# peripherals.net
KiCad netlist of a schematic drawn in Altium Designer
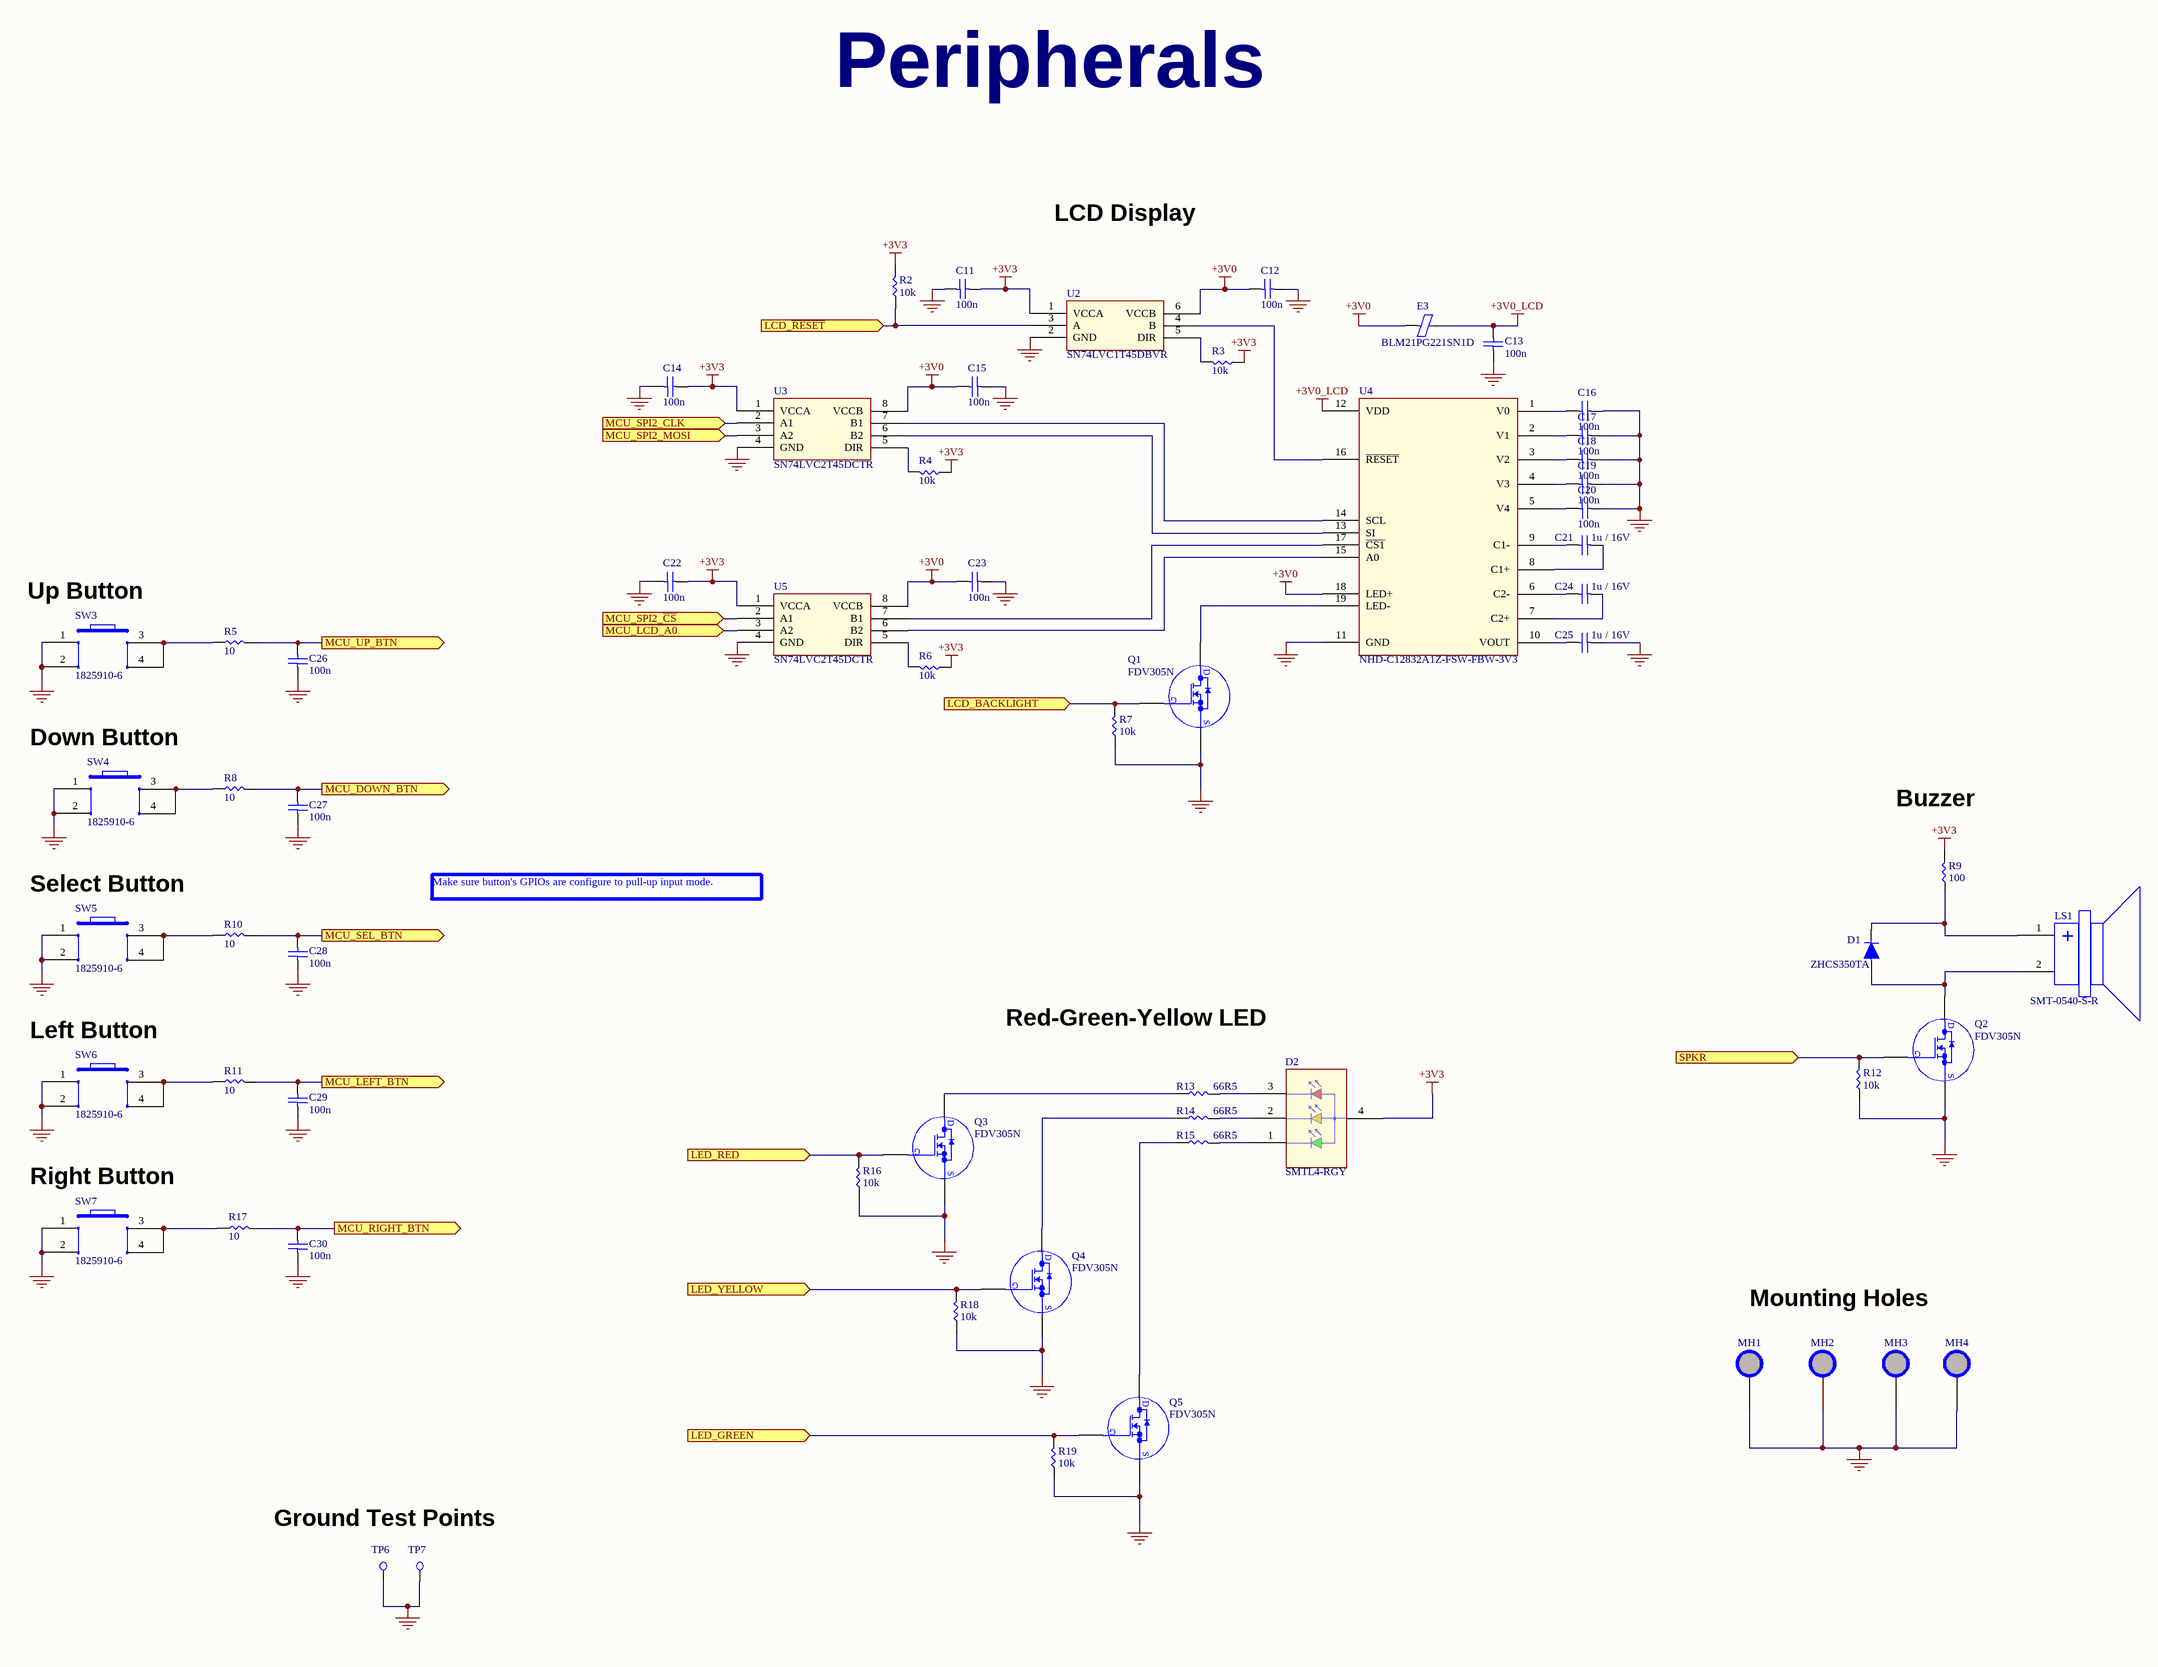
[diagram p0: peripherals.SchDoc]

(export (version "E")
  (design (tool "Eeschema 10.0.6"))
  (components
    (comp (ref "C11")
      (value "100n")
      (footprint "C0402")
      (fields
        (field (name "MANUFACTURER") "TDK")
        (field (name "PCN PART NUMBER") "MLCC Part Number Change 30/Nov/2012")
        (field (name "TOLERANCE") "±10%")
      )
      (libsource (lib "rookieboard_symbols") (part "CGA2B3X7R1E104K050BB"))
    )
    (comp (ref "C12")
      (value "100n")
      (footprint "C0402")
      (fields
        (field (name "MANUFACTURER") "TDK")
        (field (name "PCN PART NUMBER") "MLCC Part Number Change 30/Nov/2012")
        (field (name "TOLERANCE") "±10%")
      )
      (libsource (lib "rookieboard_symbols") (part "CGA2B3X7R1E104K050BB"))
    )
    (comp (ref "C13")
      (value "100n")
      (footprint "C0402")
      (fields
        (field (name "MANUFACTURER") "TDK")
        (field (name "PCN PART NUMBER") "MLCC Part Number Change 30/Nov/2012")
        (field (name "TOLERANCE") "±10%")
      )
      (libsource (lib "rookieboard_symbols") (part "CGA2B3X7R1E104K050BB"))
    )
    (comp (ref "C14")
      (value "100n")
      (footprint "C0402")
      (fields
        (field (name "MANUFACTURER") "TDK")
        (field (name "PCN PART NUMBER") "MLCC Part Number Change 30/Nov/2012")
        (field (name "TOLERANCE") "±10%")
      )
      (libsource (lib "rookieboard_symbols") (part "CGA2B3X7R1E104K050BB"))
    )
    (comp (ref "C15")
      (value "100n")
      (footprint "C0402")
      (fields
        (field (name "MANUFACTURER") "TDK")
        (field (name "PCN PART NUMBER") "MLCC Part Number Change 30/Nov/2012")
        (field (name "TOLERANCE") "±10%")
      )
      (libsource (lib "rookieboard_symbols") (part "CGA2B3X7R1E104K050BB"))
    )
    (comp (ref "C16")
      (value "100n")
      (footprint "C0402")
      (fields
        (field (name "MANUFACTURER") "TDK")
        (field (name "PCN PART NUMBER") "MLCC Part Number Change 30/Nov/2012")
        (field (name "TOLERANCE") "±10%")
      )
      (libsource (lib "rookieboard_symbols") (part "CGA2B3X7R1E104K050BB"))
    )
    (comp (ref "C17")
      (value "100n")
      (footprint "C0402")
      (fields
        (field (name "MANUFACTURER") "TDK")
        (field (name "PCN PART NUMBER") "MLCC Part Number Change 30/Nov/2012")
        (field (name "TOLERANCE") "±10%")
      )
      (libsource (lib "rookieboard_symbols") (part "CGA2B3X7R1E104K050BB"))
    )
    (comp (ref "C18")
      (value "100n")
      (footprint "C0402")
      (fields
        (field (name "MANUFACTURER") "TDK")
        (field (name "PCN PART NUMBER") "MLCC Part Number Change 30/Nov/2012")
        (field (name "TOLERANCE") "±10%")
      )
      (libsource (lib "rookieboard_symbols") (part "CGA2B3X7R1E104K050BB"))
    )
    (comp (ref "C19")
      (value "100n")
      (footprint "C0402")
      (fields
        (field (name "MANUFACTURER") "TDK")
        (field (name "PCN PART NUMBER") "MLCC Part Number Change 30/Nov/2012")
        (field (name "TOLERANCE") "±10%")
      )
      (libsource (lib "rookieboard_symbols") (part "CGA2B3X7R1E104K050BB"))
    )
    (comp (ref "C20")
      (value "100n")
      (footprint "C0402")
      (fields
        (field (name "MANUFACTURER") "TDK")
        (field (name "PCN PART NUMBER") "MLCC Part Number Change 30/Nov/2012")
        (field (name "TOLERANCE") "±10%")
      )
      (libsource (lib "rookieboard_symbols") (part "CGA2B3X7R1E104K050BB"))
    )
    (comp (ref "C21")
      (value "1u / 16V")
      (footprint "C0805")
      (description "Multilayer Ceramic Capacitors MLCC - SMD/SMT 16volts 1uF X7R 10%")
      (fields (field (name "MANUFACTURER") "KEMET") (field (name "VOLTAGE") "16 Vdc"))
      (libsource (lib "rookieboard_symbols") (part "C0805C105K4RAC7800"))
    )
    (comp (ref "C22")
      (value "100n")
      (footprint "C0402")
      (fields
        (field (name "MANUFACTURER") "TDK")
        (field (name "PCN PART NUMBER") "MLCC Part Number Change 30/Nov/2012")
        (field (name "TOLERANCE") "±10%")
      )
      (libsource (lib "rookieboard_symbols") (part "CGA2B3X7R1E104K050BB"))
    )
    (comp (ref "C23")
      (value "100n")
      (footprint "C0402")
      (fields
        (field (name "MANUFACTURER") "TDK")
        (field (name "PCN PART NUMBER") "MLCC Part Number Change 30/Nov/2012")
        (field (name "TOLERANCE") "±10%")
      )
      (libsource (lib "rookieboard_symbols") (part "CGA2B3X7R1E104K050BB"))
    )
    (comp (ref "C24")
      (value "1u / 16V")
      (footprint "C0805")
      (description "Multilayer Ceramic Capacitors MLCC - SMD/SMT 16volts 1uF X7R 10%")
      (fields (field (name "MANUFACTURER") "KEMET") (field (name "VOLTAGE") "16 Vdc"))
      (libsource (lib "rookieboard_symbols") (part "C0805C105K4RAC7800"))
    )
    (comp (ref "C25")
      (value "1u / 16V")
      (footprint "C0805")
      (description "Multilayer Ceramic Capacitors MLCC - SMD/SMT 16volts 1uF X7R 10%")
      (fields (field (name "MANUFACTURER") "KEMET") (field (name "VOLTAGE") "16 Vdc"))
      (libsource (lib "rookieboard_symbols") (part "C0805C105K4RAC7800"))
    )
    (comp (ref "C26")
      (value "100n")
      (footprint "C0402")
      (fields
        (field (name "MANUFACTURER") "TDK")
        (field (name "PCN PART NUMBER") "MLCC Part Number Change 30/Nov/2012")
        (field (name "TOLERANCE") "±10%")
      )
      (libsource (lib "rookieboard_symbols") (part "CGA2B3X7R1E104K050BB"))
    )
    (comp (ref "C27")
      (value "100n")
      (footprint "C0402")
      (fields
        (field (name "MANUFACTURER") "TDK")
        (field (name "PCN PART NUMBER") "MLCC Part Number Change 30/Nov/2012")
        (field (name "TOLERANCE") "±10%")
      )
      (libsource (lib "rookieboard_symbols") (part "CGA2B3X7R1E104K050BB"))
    )
    (comp (ref "C28")
      (value "100n")
      (footprint "C0402")
      (fields
        (field (name "MANUFACTURER") "TDK")
        (field (name "PCN PART NUMBER") "MLCC Part Number Change 30/Nov/2012")
        (field (name "TOLERANCE") "±10%")
      )
      (libsource (lib "rookieboard_symbols") (part "CGA2B3X7R1E104K050BB"))
    )
    (comp (ref "C29")
      (value "100n")
      (footprint "C0402")
      (fields
        (field (name "MANUFACTURER") "TDK")
        (field (name "PCN PART NUMBER") "MLCC Part Number Change 30/Nov/2012")
        (field (name "TOLERANCE") "±10%")
      )
      (libsource (lib "rookieboard_symbols") (part "CGA2B3X7R1E104K050BB"))
    )
    (comp (ref "C30")
      (value "100n")
      (footprint "C0402")
      (fields
        (field (name "MANUFACTURER") "TDK")
        (field (name "PCN PART NUMBER") "MLCC Part Number Change 30/Nov/2012")
        (field (name "TOLERANCE") "±10%")
      )
      (libsource (lib "rookieboard_symbols") (part "CGA2B3X7R1E104K050BB"))
    )
    (comp (ref "D1")
      (value "ZHCS350TA")
      (footprint "DIODE_SOD-523")
      (description "DIODE SCHOTTKY 40V 350MA SOD523")
      (fields (field (name "MANUFACTURER") "Diodes Zetex"))
      (libsource (lib "rookieboard_symbols") (part "ZHCS350TA"))
    )
    (comp (ref "D2")
      (value "SMTL4-RGY")
      (footprint "SMTL4-RGY")
      (fields (field (name "MANUFACTURER") "Bivar"))
      (libsource (lib "rookieboard_symbols") (part "SMTL4-RGY"))
    )
    (comp (ref "E3")
      (value "BLM21PG221SN1D")
      (footprint "R0805")
      (description "FERRITE CHIP 220 OHM 0805")
      (fields (field (name "MANUFACTURER") "Murata"))
      (libsource (lib "rookieboard_symbols") (part "BLM21PG221SN1D"))
    )
    (comp (ref "LS1")
      (value "SMT-0540-S-R")
      (footprint "SMT-0540-S-R")
      (description "BUZZER MAGNETIC 3V 5MM SMD")
      (fields (field (name "MANUFACTURER") "Projects Unlimited"))
      (libsource (lib "rookieboard_symbols") (part "SMT-0540-S-R"))
    )
    (comp (ref "MH1")
      (value "Mounting Hole 7.4mm, 3.2mm")
      (footprint "MH_7.4mm_3.2mm")
      (libsource (lib "rookieboard_symbols") (part "MOUNT_HOLE_7.4mm_3.2mm"))
    )
    (comp (ref "MH2")
      (value "Mounting Hole 7.4mm, 3.2mm")
      (footprint "MH_7.4mm_3.2mm")
      (libsource (lib "rookieboard_symbols") (part "MOUNT_HOLE_7.4mm_3.2mm"))
    )
    (comp (ref "MH3")
      (value "Mounting Hole 7.4mm, 3.2mm")
      (footprint "MH_7.4mm_3.2mm")
      (libsource (lib "rookieboard_symbols") (part "MOUNT_HOLE_7.4mm_3.2mm"))
    )
    (comp (ref "MH4")
      (value "Mounting Hole 7.4mm, 3.2mm")
      (footprint "MH_7.4mm_3.2mm")
      (libsource (lib "rookieboard_symbols") (part "MOUNT_HOLE_7.4mm_3.2mm"))
    )
    (comp (ref "Q1")
      (value "FDV305N")
      (footprint "FDV305N_SOT-23-3")
      (description "MOSFET N-CH 20V 0.9A SOT-23")
      (fields (field (name "MANUFACTURER") "ON Semiconductor / Fairchild"))
      (libsource (lib "rookieboard_symbols") (part "FDV305N"))
    )
    (comp (ref "Q2")
      (value "FDV305N")
      (footprint "FDV305N_SOT-23-3")
      (description "MOSFET N-CH 20V 0.9A SOT-23")
      (fields (field (name "MANUFACTURER") "ON Semiconductor / Fairchild"))
      (libsource (lib "rookieboard_symbols") (part "FDV305N"))
    )
    (comp (ref "Q3")
      (value "FDV305N")
      (footprint "FDV305N_SOT-23-3")
      (description "MOSFET N-CH 20V 0.9A SOT-23")
      (fields (field (name "MANUFACTURER") "ON Semiconductor / Fairchild"))
      (libsource (lib "rookieboard_symbols") (part "FDV305N"))
    )
    (comp (ref "Q4")
      (value "FDV305N")
      (footprint "FDV305N_SOT-23-3")
      (description "MOSFET N-CH 20V 0.9A SOT-23")
      (fields (field (name "MANUFACTURER") "ON Semiconductor / Fairchild"))
      (libsource (lib "rookieboard_symbols") (part "FDV305N"))
    )
    (comp (ref "Q5")
      (value "FDV305N")
      (footprint "FDV305N_SOT-23-3")
      (description "MOSFET N-CH 20V 0.9A SOT-23")
      (fields (field (name "MANUFACTURER") "ON Semiconductor / Fairchild"))
      (libsource (lib "rookieboard_symbols") (part "FDV305N"))
    )
    (comp (ref "R2")
      (value "10k")
      (footprint "R0805")
      (description "RES SMD 10K OHM 1% 1/8W 0805")
      (fields (field (name "MANUFACTURER") "Yageo") (field (name "TOLERANCE") "1 %"))
      (libsource (lib "rookieboard_symbols") (part "RC0805FR-0710KL"))
    )
    (comp (ref "R3")
      (value "10k")
      (footprint "R0805")
      (description "RES SMD 10K OHM 1% 1/8W 0805")
      (fields (field (name "MANUFACTURER") "Yageo") (field (name "TOLERANCE") "1 %"))
      (libsource (lib "rookieboard_symbols") (part "RC0805FR-0710KL"))
    )
    (comp (ref "R4")
      (value "10k")
      (footprint "R0805")
      (description "RES SMD 10K OHM 1% 1/8W 0805")
      (fields (field (name "MANUFACTURER") "Yageo") (field (name "TOLERANCE") "1 %"))
      (libsource (lib "rookieboard_symbols") (part "RC0805FR-0710KL"))
    )
    (comp (ref "R5")
      (value "10")
      (footprint "R0402")
      (description "RES SMD 10 OHM 1% 1/16W 0402")
      (fields (field (name "MANUFACTURER") "Yageo") (field (name "TOLERANCE") "1 %"))
      (libsource (lib "rookieboard_symbols") (part "RC0402FR-0710RL"))
    )
    (comp (ref "R6")
      (value "10k")
      (footprint "R0805")
      (description "RES SMD 10K OHM 1% 1/8W 0805")
      (fields (field (name "MANUFACTURER") "Yageo") (field (name "TOLERANCE") "1 %"))
      (libsource (lib "rookieboard_symbols") (part "RC0805FR-0710KL"))
    )
    (comp (ref "R7")
      (value "10k")
      (footprint "R0805")
      (description "RES SMD 10K OHM 1% 1/8W 0805")
      (fields (field (name "MANUFACTURER") "Yageo") (field (name "TOLERANCE") "1 %"))
      (libsource (lib "rookieboard_symbols") (part "RC0805FR-0710KL"))
    )
    (comp (ref "R8")
      (value "10")
      (footprint "R0402")
      (description "RES SMD 10 OHM 1% 1/16W 0402")
      (fields (field (name "MANUFACTURER") "Yageo") (field (name "TOLERANCE") "1 %"))
      (libsource (lib "rookieboard_symbols") (part "RC0402FR-0710RL"))
    )
    (comp (ref "R9")
      (value "100")
      (footprint "R0805")
      (description "RES SMD 100 OHM 1% 1/8W 0805")
      (fields (field (name "MANUFACTURER") "Yageo") (field (name "TOLERANCE") "1 %"))
      (libsource (lib "rookieboard_symbols") (part "RT0805FRE07100RL"))
    )
    (comp (ref "R10")
      (value "10")
      (footprint "R0402")
      (description "RES SMD 10 OHM 1% 1/16W 0402")
      (fields (field (name "MANUFACTURER") "Yageo") (field (name "TOLERANCE") "1 %"))
      (libsource (lib "rookieboard_symbols") (part "RC0402FR-0710RL"))
    )
    (comp (ref "R11")
      (value "10")
      (footprint "R0402")
      (description "RES SMD 10 OHM 1% 1/16W 0402")
      (fields (field (name "MANUFACTURER") "Yageo") (field (name "TOLERANCE") "1 %"))
      (libsource (lib "rookieboard_symbols") (part "RC0402FR-0710RL"))
    )
    (comp (ref "R12")
      (value "10k")
      (footprint "R0805")
      (description "RES SMD 10K OHM 1% 1/8W 0805")
      (fields (field (name "MANUFACTURER") "Yageo") (field (name "TOLERANCE") "1 %"))
      (libsource (lib "rookieboard_symbols") (part "RC0805FR-0710KL"))
    )
    (comp (ref "R13")
      (value "66R5")
      (footprint "R0805")
      (description "Thick Film Resistors - SMD 66.5 OHM 1%")
      (fields (field (name "MANUFACTURER") "Yageo") (field (name "TOLERANCE") "1 %"))
      (libsource (lib "rookieboard_symbols") (part "RC0805FR-0766R5L"))
    )
    (comp (ref "R14")
      (value "66R5")
      (footprint "R0805")
      (description "Thick Film Resistors - SMD 66.5 OHM 1%")
      (fields (field (name "MANUFACTURER") "Yageo") (field (name "TOLERANCE") "1 %"))
      (libsource (lib "rookieboard_symbols") (part "RC0805FR-0766R5L"))
    )
    (comp (ref "R15")
      (value "66R5")
      (footprint "R0805")
      (description "Thick Film Resistors - SMD 66.5 OHM 1%")
      (fields (field (name "MANUFACTURER") "Yageo") (field (name "TOLERANCE") "1 %"))
      (libsource (lib "rookieboard_symbols") (part "RC0805FR-0766R5L"))
    )
    (comp (ref "R16")
      (value "10k")
      (footprint "R0805")
      (description "RES SMD 10K OHM 1% 1/8W 0805")
      (fields (field (name "MANUFACTURER") "Yageo") (field (name "TOLERANCE") "1 %"))
      (libsource (lib "rookieboard_symbols") (part "RC0805FR-0710KL"))
    )
    (comp (ref "R17")
      (value "10")
      (footprint "R0402")
      (description "RES SMD 10 OHM 1% 1/16W 0402")
      (fields (field (name "MANUFACTURER") "Yageo") (field (name "TOLERANCE") "1 %"))
      (libsource (lib "rookieboard_symbols") (part "RC0402FR-0710RL"))
    )
    (comp (ref "R18")
      (value "10k")
      (footprint "R0805")
      (description "RES SMD 10K OHM 1% 1/8W 0805")
      (fields (field (name "MANUFACTURER") "Yageo") (field (name "TOLERANCE") "1 %"))
      (libsource (lib "rookieboard_symbols") (part "RC0805FR-0710KL"))
    )
    (comp (ref "R19")
      (value "10k")
      (footprint "R0805")
      (description "RES SMD 10K OHM 1% 1/8W 0805")
      (fields (field (name "MANUFACTURER") "Yageo") (field (name "TOLERANCE") "1 %"))
      (libsource (lib "rookieboard_symbols") (part "RC0805FR-0710KL"))
    )
    (comp (ref "SW3")
      (value "1825910-6")
      (footprint "1825910-6")
      (description "Switch Push Button OFF (ON) SPST Round Button 0.05A 24VDC Momentary Contact PC Pins Thru-Hole")
      (fields (field (name "MANUFACTURER") "TE Connectivity Alcoswitch"))
      (libsource (lib "rookieboard_symbols") (part "1825910-6"))
    )
    (comp (ref "SW4")
      (value "1825910-6")
      (footprint "1825910-6")
      (description "Switch Push Button OFF (ON) SPST Round Button 0.05A 24VDC Momentary Contact PC Pins Thru-Hole")
      (fields (field (name "MANUFACTURER") "TE Connectivity Alcoswitch"))
      (libsource (lib "rookieboard_symbols") (part "1825910-6"))
    )
    (comp (ref "SW5")
      (value "1825910-6")
      (footprint "1825910-6")
      (description "Switch Push Button OFF (ON) SPST Round Button 0.05A 24VDC Momentary Contact PC Pins Thru-Hole")
      (fields (field (name "MANUFACTURER") "TE Connectivity Alcoswitch"))
      (libsource (lib "rookieboard_symbols") (part "1825910-6"))
    )
    (comp (ref "SW6")
      (value "1825910-6")
      (footprint "1825910-6")
      (description "Switch Push Button OFF (ON) SPST Round Button 0.05A 24VDC Momentary Contact PC Pins Thru-Hole")
      (fields (field (name "MANUFACTURER") "TE Connectivity Alcoswitch"))
      (libsource (lib "rookieboard_symbols") (part "1825910-6"))
    )
    (comp (ref "SW7")
      (value "1825910-6")
      (footprint "1825910-6")
      (description "Switch Push Button OFF (ON) SPST Round Button 0.05A 24VDC Momentary Contact PC Pins Thru-Hole")
      (fields (field (name "MANUFACTURER") "TE Connectivity Alcoswitch"))
      (libsource (lib "rookieboard_symbols") (part "1825910-6"))
    )
    (comp (ref "TP6")
      (value "Test Pad 1mm")
      (footprint "TP_1MM")
      (libsource (lib "rookieboard_symbols") (part "TEST_PAD_1mm"))
    )
    (comp (ref "TP7")
      (value "Test Pad 1mm")
      (footprint "TP_1MM")
      (libsource (lib "rookieboard_symbols") (part "TEST_PAD_1mm"))
    )
    (comp (ref "U2")
      (value "SN74LVC1T45DBVR")
      (footprint "SOT-23-6")
      (fields (field (name "MANUFACTURER") "Texas Instruments"))
      (libsource (lib "rookieboard_symbols") (part "SN74LVC1T45DBVR"))
    )
    (comp (ref "U3")
      (value "SN74LVC2T45DCTR")
      (footprint "SOP8")
      (description "IC, 2BIT BUS TRANSCEIVER, SSOP-8")
      (fields (field (name "MANUFACTURER") "Texas Instruments"))
      (libsource (lib "rookieboard_symbols") (part "SN74LVC2T45DCTR"))
    )
    (comp (ref "U4")
      (value "NHD-C12832A1Z-FSW-FBW-3V3")
      (footprint "NHD-C12832A1Z-FSW-FBW-3V3")
      (description "LCD COG GRAPHIC 128X32")
      (fields (field (name "MANUFACTURER") "Newhaven Display"))
      (libsource (lib "rookieboard_symbols") (part "NHD-C12832A1Z-FSW-FBW-3V3"))
    )
    (comp (ref "U5")
      (value "SN74LVC2T45DCTR")
      (footprint "SOP8")
      (description "IC, 2BIT BUS TRANSCEIVER, SSOP-8")
      (fields (field (name "MANUFACTURER") "Texas Instruments"))
      (libsource (lib "rookieboard_symbols") (part "SN74LVC2T45DCTR"))
    )
  )
  (nets
    (net (code "1") (name "+3V0") (class "Default")
      (node (ref "C12") (pin "1") (pinfunction "1_1") (pintype "passive"))
      (node (ref "C15") (pin "2") (pinfunction "2_2") (pintype "passive"))
      (node (ref "C23") (pin "2") (pinfunction "2_2") (pintype "passive"))
      (node (ref "E3") (pin "1") (pinfunction "1_1") (pintype "passive"))
      (node (ref "U2") (pin "6") (pinfunction "VCCB_6") (pintype "power_in"))
      (node (ref "U3") (pin "8") (pinfunction "VCCB_8") (pintype "power_in"))
      (node (ref "U4") (pin "18") (pinfunction "LED+_18") (pintype "passive"))
      (node (ref "U5") (pin "8") (pinfunction "VCCB_8") (pintype "power_in"))
    )
    (net (code "2") (name "+3V0_LCD") (class "Default")
      (node (ref "C13") (pin "2") (pinfunction "2_2") (pintype "passive"))
      (node (ref "E3") (pin "2") (pinfunction "2_2") (pintype "passive"))
      (node (ref "U4") (pin "12") (pinfunction "VDD_12") (pintype "power_in"))
    )
    (net (code "3") (name "+3V3") (class "Default")
      (node (ref "C11") (pin "2") (pinfunction "2_2") (pintype "passive"))
      (node (ref "C14") (pin "2") (pinfunction "2_2") (pintype "passive"))
      (node (ref "C22") (pin "2") (pinfunction "2_2") (pintype "passive"))
      (node (ref "D2") (pin "4") (pinfunction "COMMON_ANODE_4") (pintype "passive"))
      (node (ref "R2") (pin "2") (pinfunction "2_2") (pintype "passive"))
      (node (ref "R3") (pin "1") (pinfunction "1_1") (pintype "passive"))
      (node (ref "R4") (pin "1") (pinfunction "1_1") (pintype "passive"))
      (node (ref "R6") (pin "1") (pinfunction "1_1") (pintype "passive"))
      (node (ref "R9") (pin "2") (pinfunction "2_2") (pintype "passive"))
      (node (ref "U2") (pin "1") (pinfunction "VCCA_1") (pintype "power_in"))
      (node (ref "U3") (pin "1") (pinfunction "VCCA_1") (pintype "power_in"))
      (node (ref "U5") (pin "1") (pinfunction "VCCA_1") (pintype "power_in"))
    )
    (net (code "4") (name "/LCD_BACKLIGHT") (class "Default")
      (node (ref "Q1") (pin "1") (pinfunction "G_1") (pintype "passive"))
      (node (ref "R7") (pin "2") (pinfunction "2_2") (pintype "passive"))
    )
    (net (code "5") (name "/LCD_~{RESET}") (class "Default")
      (node (ref "R2") (pin "1") (pinfunction "1_1") (pintype "passive"))
      (node (ref "U2") (pin "3") (pinfunction "A_3") (pintype "passive"))
    )
    (net (code "6") (name "/LED_GREEN") (class "Default")
      (node (ref "Q5") (pin "1") (pinfunction "G_1") (pintype "passive"))
      (node (ref "R19") (pin "2") (pinfunction "2_2") (pintype "passive"))
    )
    (net (code "7") (name "/LED_RED") (class "Default")
      (node (ref "Q3") (pin "1") (pinfunction "G_1") (pintype "passive"))
      (node (ref "R16") (pin "2") (pinfunction "2_2") (pintype "passive"))
    )
    (net (code "8") (name "/LED_YELLOW") (class "Default")
      (node (ref "Q4") (pin "1") (pinfunction "G_1") (pintype "passive"))
      (node (ref "R18") (pin "2") (pinfunction "2_2") (pintype "passive"))
    )
    (net (code "9") (name "/MCU_DOWN_BTN") (class "Default")
      (node (ref "C27") (pin "2") (pinfunction "2_2") (pintype "passive"))
      (node (ref "R8") (pin "2") (pinfunction "2_2") (pintype "passive"))
    )
    (net (code "10") (name "/MCU_LCD_A0") (class "Default")
      (node (ref "U5") (pin "3") (pinfunction "A2_3") (pintype "passive"))
    )
    (net (code "11") (name "/MCU_LEFT_BTN") (class "Default")
      (node (ref "C29") (pin "2") (pinfunction "2_2") (pintype "passive"))
      (node (ref "R11") (pin "2") (pinfunction "2_2") (pintype "passive"))
    )
    (net (code "12") (name "/MCU_RIGHT_BTN") (class "Default")
      (node (ref "C30") (pin "2") (pinfunction "2_2") (pintype "passive"))
      (node (ref "R17") (pin "2") (pinfunction "2_2") (pintype "passive"))
    )
    (net (code "13") (name "/MCU_SEL_BTN") (class "Default")
      (node (ref "C28") (pin "2") (pinfunction "2_2") (pintype "passive"))
      (node (ref "R10") (pin "2") (pinfunction "2_2") (pintype "passive"))
    )
    (net (code "14") (name "/MCU_SPI2_CLK") (class "Default")
      (node (ref "U3") (pin "2") (pinfunction "A1_2") (pintype "passive"))
    )
    (net (code "15") (name "/MCU_SPI2_MOSI") (class "Default")
      (node (ref "U3") (pin "3") (pinfunction "A2_3") (pintype "passive"))
    )
    (net (code "16") (name "/MCU_SPI2_~{CS}") (class "Default")
      (node (ref "U5") (pin "2") (pinfunction "A1_2") (pintype "passive"))
    )
    (net (code "17") (name "/MCU_UP_BTN") (class "Default")
      (node (ref "C26") (pin "2") (pinfunction "2_2") (pintype "passive"))
      (node (ref "R5") (pin "2") (pinfunction "2_2") (pintype "passive"))
    )
    (net (code "18") (name "/SPKR") (class "Default")
      (node (ref "Q2") (pin "1") (pinfunction "G_1") (pintype "passive"))
      (node (ref "R12") (pin "2") (pinfunction "2_2") (pintype "passive"))
    )
    (net (code "19") (name "GND") (class "Default")
      (node (ref "C11") (pin "1") (pinfunction "1_1") (pintype "passive"))
      (node (ref "C12") (pin "2") (pinfunction "2_2") (pintype "passive"))
      (node (ref "C13") (pin "1") (pinfunction "1_1") (pintype "passive"))
      (node (ref "C14") (pin "1") (pinfunction "1_1") (pintype "passive"))
      (node (ref "C15") (pin "1") (pinfunction "1_1") (pintype "passive"))
      (node (ref "C16") (pin "2") (pinfunction "2_2") (pintype "passive"))
      (node (ref "C17") (pin "2") (pinfunction "2_2") (pintype "passive"))
      (node (ref "C18") (pin "2") (pinfunction "2_2") (pintype "passive"))
      (node (ref "C19") (pin "2") (pinfunction "2_2") (pintype "passive"))
      (node (ref "C20") (pin "2") (pinfunction "2_2") (pintype "passive"))
      (node (ref "C22") (pin "1") (pinfunction "1_1") (pintype "passive"))
      (node (ref "C23") (pin "1") (pinfunction "1_1") (pintype "passive"))
      (node (ref "C25") (pin "1") (pinfunction "1_1") (pintype "passive"))
      (node (ref "C26") (pin "1") (pinfunction "1_1") (pintype "passive"))
      (node (ref "C27") (pin "1") (pinfunction "1_1") (pintype "passive"))
      (node (ref "C28") (pin "1") (pinfunction "1_1") (pintype "passive"))
      (node (ref "C29") (pin "1") (pinfunction "1_1") (pintype "passive"))
      (node (ref "C30") (pin "1") (pinfunction "1_1") (pintype "passive"))
      (node (ref "MH1") (pin "1") (pinfunction "1_1") (pintype "passive"))
      (node (ref "MH2") (pin "1") (pinfunction "1_1") (pintype "passive"))
      (node (ref "MH3") (pin "1") (pinfunction "1_1") (pintype "passive"))
      (node (ref "MH4") (pin "1") (pinfunction "1_1") (pintype "passive"))
      (node (ref "Q1") (pin "2") (pinfunction "S_2") (pintype "passive"))
      (node (ref "Q2") (pin "2") (pinfunction "S_2") (pintype "passive"))
      (node (ref "Q3") (pin "2") (pinfunction "S_2") (pintype "passive"))
      (node (ref "Q4") (pin "2") (pinfunction "S_2") (pintype "passive"))
      (node (ref "Q5") (pin "2") (pinfunction "S_2") (pintype "passive"))
      (node (ref "R12") (pin "1") (pinfunction "1_1") (pintype "passive"))
      (node (ref "R16") (pin "1") (pinfunction "1_1") (pintype "passive"))
      (node (ref "R18") (pin "1") (pinfunction "1_1") (pintype "passive"))
      (node (ref "R19") (pin "1") (pinfunction "1_1") (pintype "passive"))
      (node (ref "R7") (pin "1") (pinfunction "1_1") (pintype "passive"))
      (node (ref "SW3") (pin "1") (pinfunction "1_1") (pintype "passive"))
      (node (ref "SW3") (pin "2") (pinfunction "2_2") (pintype "passive"))
      (node (ref "SW4") (pin "1") (pinfunction "1_1") (pintype "passive"))
      (node (ref "SW4") (pin "2") (pinfunction "2_2") (pintype "passive"))
      (node (ref "SW5") (pin "1") (pinfunction "1_1") (pintype "passive"))
      (node (ref "SW5") (pin "2") (pinfunction "2_2") (pintype "passive"))
      (node (ref "SW6") (pin "1") (pinfunction "1_1") (pintype "passive"))
      (node (ref "SW6") (pin "2") (pinfunction "2_2") (pintype "passive"))
      (node (ref "SW7") (pin "1") (pinfunction "1_1") (pintype "passive"))
      (node (ref "SW7") (pin "2") (pinfunction "2_2") (pintype "passive"))
      (node (ref "TP6") (pin "1") (pinfunction "1_1") (pintype "passive"))
      (node (ref "TP7") (pin "1") (pinfunction "1_1") (pintype "passive"))
      (node (ref "U2") (pin "2") (pinfunction "GND_2") (pintype "power_in"))
      (node (ref "U3") (pin "4") (pinfunction "GND_4") (pintype "power_in"))
      (node (ref "U4") (pin "11") (pinfunction "GND_11") (pintype "power_in"))
      (node (ref "U5") (pin "4") (pinfunction "GND_4") (pintype "power_in"))
    )
    (net (code "20") (name "Net-(D1-A)") (class "Default")
      (node (ref "D1") (pin "1") (pinfunction "A_1") (pintype "passive"))
      (node (ref "LS1") (pin "2") (pinfunction "+_2") (pintype "passive"))
      (node (ref "Q2") (pin "3") (pinfunction "D_3") (pintype "passive"))
    )
    (net (code "21") (name "Net-(D1-K)") (class "Default")
      (node (ref "D1") (pin "2") (pinfunction "K_2") (pintype "passive"))
      (node (ref "LS1") (pin "1") (pinfunction "+_1") (pintype "passive"))
      (node (ref "R9") (pin "1") (pinfunction "1_1") (pintype "passive"))
    )
    (net (code "22") (name "Net-(D2-GREEN_CATHODE)") (class "Default")
      (node (ref "D2") (pin "1") (pinfunction "GREEN_CATHODE_1") (pintype "passive"))
      (node (ref "R15") (pin "2") (pinfunction "2_2") (pintype "passive"))
    )
    (net (code "23") (name "Net-(D2-RED_CATHODE)") (class "Default")
      (node (ref "D2") (pin "3") (pinfunction "RED_CATHODE_3") (pintype "passive"))
      (node (ref "R13") (pin "2") (pinfunction "2_2") (pintype "passive"))
    )
    (net (code "24") (name "Net-(D2-YELLOW_CATHODE)") (class "Default")
      (node (ref "D2") (pin "2") (pinfunction "YELLOW_CATHODE_2") (pintype "passive"))
      (node (ref "R14") (pin "2") (pinfunction "2_2") (pintype "passive"))
    )
    (net (code "25") (name "Net-(Q1-D)") (class "Default")
      (node (ref "Q1") (pin "3") (pinfunction "D_3") (pintype "passive"))
      (node (ref "U4") (pin "19") (pinfunction "LED-_19") (pintype "passive"))
    )
    (net (code "26") (name "Net-(Q3-D)") (class "Default")
      (node (ref "Q3") (pin "3") (pinfunction "D_3") (pintype "passive"))
      (node (ref "R13") (pin "1") (pinfunction "1_1") (pintype "passive"))
    )
    (net (code "27") (name "Net-(Q4-D)") (class "Default")
      (node (ref "Q4") (pin "3") (pinfunction "D_3") (pintype "passive"))
      (node (ref "R14") (pin "1") (pinfunction "1_1") (pintype "passive"))
    )
    (net (code "28") (name "Net-(Q5-D)") (class "Default")
      (node (ref "Q5") (pin "3") (pinfunction "D_3") (pintype "passive"))
      (node (ref "R15") (pin "1") (pinfunction "1_1") (pintype "passive"))
    )
    (net (code "29") (name "Net-(R5-Pad1)") (class "Default")
      (node (ref "R5") (pin "1") (pinfunction "1_1") (pintype "passive"))
      (node (ref "SW3") (pin "3") (pinfunction "3_3") (pintype "passive"))
      (node (ref "SW3") (pin "4") (pinfunction "4_4") (pintype "passive"))
    )
    (net (code "30") (name "Net-(R8-Pad1)") (class "Default")
      (node (ref "R8") (pin "1") (pinfunction "1_1") (pintype "passive"))
      (node (ref "SW4") (pin "3") (pinfunction "3_3") (pintype "passive"))
      (node (ref "SW4") (pin "4") (pinfunction "4_4") (pintype "passive"))
    )
    (net (code "31") (name "Net-(R10-Pad1)") (class "Default")
      (node (ref "R10") (pin "1") (pinfunction "1_1") (pintype "passive"))
      (node (ref "SW5") (pin "3") (pinfunction "3_3") (pintype "passive"))
      (node (ref "SW5") (pin "4") (pinfunction "4_4") (pintype "passive"))
    )
    (net (code "32") (name "Net-(R11-Pad1)") (class "Default")
      (node (ref "R11") (pin "1") (pinfunction "1_1") (pintype "passive"))
      (node (ref "SW6") (pin "3") (pinfunction "3_3") (pintype "passive"))
      (node (ref "SW6") (pin "4") (pinfunction "4_4") (pintype "passive"))
    )
    (net (code "33") (name "Net-(R17-Pad1)") (class "Default")
      (node (ref "R17") (pin "1") (pinfunction "1_1") (pintype "passive"))
      (node (ref "SW7") (pin "3") (pinfunction "3_3") (pintype "passive"))
      (node (ref "SW7") (pin "4") (pinfunction "4_4") (pintype "passive"))
    )
    (net (code "34") (name "Net-(U2-B)") (class "Default")
      (node (ref "U2") (pin "4") (pinfunction "B_4") (pintype "passive"))
      (node (ref "U4") (pin "16") (pinfunction "~{RESET}_16") (pintype "passive"))
    )
    (net (code "35") (name "Net-(U2-DIR)") (class "Default")
      (node (ref "R3") (pin "2") (pinfunction "2_2") (pintype "passive"))
      (node (ref "U2") (pin "5") (pinfunction "DIR_5") (pintype "passive"))
    )
    (net (code "36") (name "Net-(U3-B1)") (class "Default")
      (node (ref "U3") (pin "7") (pinfunction "B1_7") (pintype "passive"))
      (node (ref "U4") (pin "14") (pinfunction "SCL_14") (pintype "passive"))
    )
    (net (code "37") (name "Net-(U3-B2)") (class "Default")
      (node (ref "U3") (pin "6") (pinfunction "B2_6") (pintype "passive"))
      (node (ref "U4") (pin "13") (pinfunction "SI_13") (pintype "passive"))
    )
    (net (code "38") (name "Net-(U3-DIR)") (class "Default")
      (node (ref "R4") (pin "2") (pinfunction "2_2") (pintype "passive"))
      (node (ref "U3") (pin "5") (pinfunction "DIR_5") (pintype "passive"))
    )
    (net (code "39") (name "Net-(U4-A0)") (class "Default")
      (node (ref "U4") (pin "15") (pinfunction "A0_15") (pintype "passive"))
      (node (ref "U5") (pin "6") (pinfunction "B2_6") (pintype "passive"))
    )
    (net (code "40") (name "Net-(U4-C1+)") (class "Default")
      (node (ref "C21") (pin "1") (pinfunction "1_1") (pintype "passive"))
      (node (ref "U4") (pin "8") (pinfunction "C1+_8") (pintype "power_in"))
    )
    (net (code "41") (name "Net-(U4-C1-)") (class "Default")
      (node (ref "C21") (pin "2") (pinfunction "2_2") (pintype "passive"))
      (node (ref "U4") (pin "9") (pinfunction "C1-_9") (pintype "power_in"))
    )
    (net (code "42") (name "Net-(U4-C2+)") (class "Default")
      (node (ref "C24") (pin "1") (pinfunction "1_1") (pintype "passive"))
      (node (ref "U4") (pin "7") (pinfunction "C2+_7") (pintype "power_in"))
    )
    (net (code "43") (name "Net-(U4-C2-)") (class "Default")
      (node (ref "C24") (pin "2") (pinfunction "2_2") (pintype "passive"))
      (node (ref "U4") (pin "6") (pinfunction "C2-_6") (pintype "power_in"))
    )
    (net (code "44") (name "Net-(U4-V0)") (class "Default")
      (node (ref "C16") (pin "1") (pinfunction "1_1") (pintype "passive"))
      (node (ref "U4") (pin "1") (pinfunction "V0_1") (pintype "power_in"))
    )
    (net (code "45") (name "Net-(U4-V1)") (class "Default")
      (node (ref "C17") (pin "1") (pinfunction "1_1") (pintype "passive"))
      (node (ref "U4") (pin "2") (pinfunction "V1_2") (pintype "power_in"))
    )
    (net (code "46") (name "Net-(U4-V2)") (class "Default")
      (node (ref "C18") (pin "1") (pinfunction "1_1") (pintype "passive"))
      (node (ref "U4") (pin "3") (pinfunction "V2_3") (pintype "power_in"))
    )
    (net (code "47") (name "Net-(U4-V3)") (class "Default")
      (node (ref "C19") (pin "1") (pinfunction "1_1") (pintype "passive"))
      (node (ref "U4") (pin "4") (pinfunction "V3_4") (pintype "power_in"))
    )
    (net (code "48") (name "Net-(U4-V4)") (class "Default")
      (node (ref "C20") (pin "1") (pinfunction "1_1") (pintype "passive"))
      (node (ref "U4") (pin "5") (pinfunction "V4_5") (pintype "power_in"))
    )
    (net (code "49") (name "Net-(U4-VOUT)") (class "Default")
      (node (ref "C25") (pin "2") (pinfunction "2_2") (pintype "passive"))
      (node (ref "U4") (pin "10") (pinfunction "VOUT_10") (pintype "power_in"))
    )
    (net (code "50") (name "Net-(U4-~{CS1})") (class "Default")
      (node (ref "U4") (pin "17") (pinfunction "~{CS1}_17") (pintype "passive"))
      (node (ref "U5") (pin "7") (pinfunction "B1_7") (pintype "passive"))
    )
    (net (code "51") (name "Net-(U5-DIR)") (class "Default")
      (node (ref "R6") (pin "2") (pinfunction "2_2") (pintype "passive"))
      (node (ref "U5") (pin "5") (pinfunction "DIR_5") (pintype "passive"))
    )
  )
)
